# coin_cell_temp_sensor.net
KiCad netlist of a schematic drawn in EAGLE
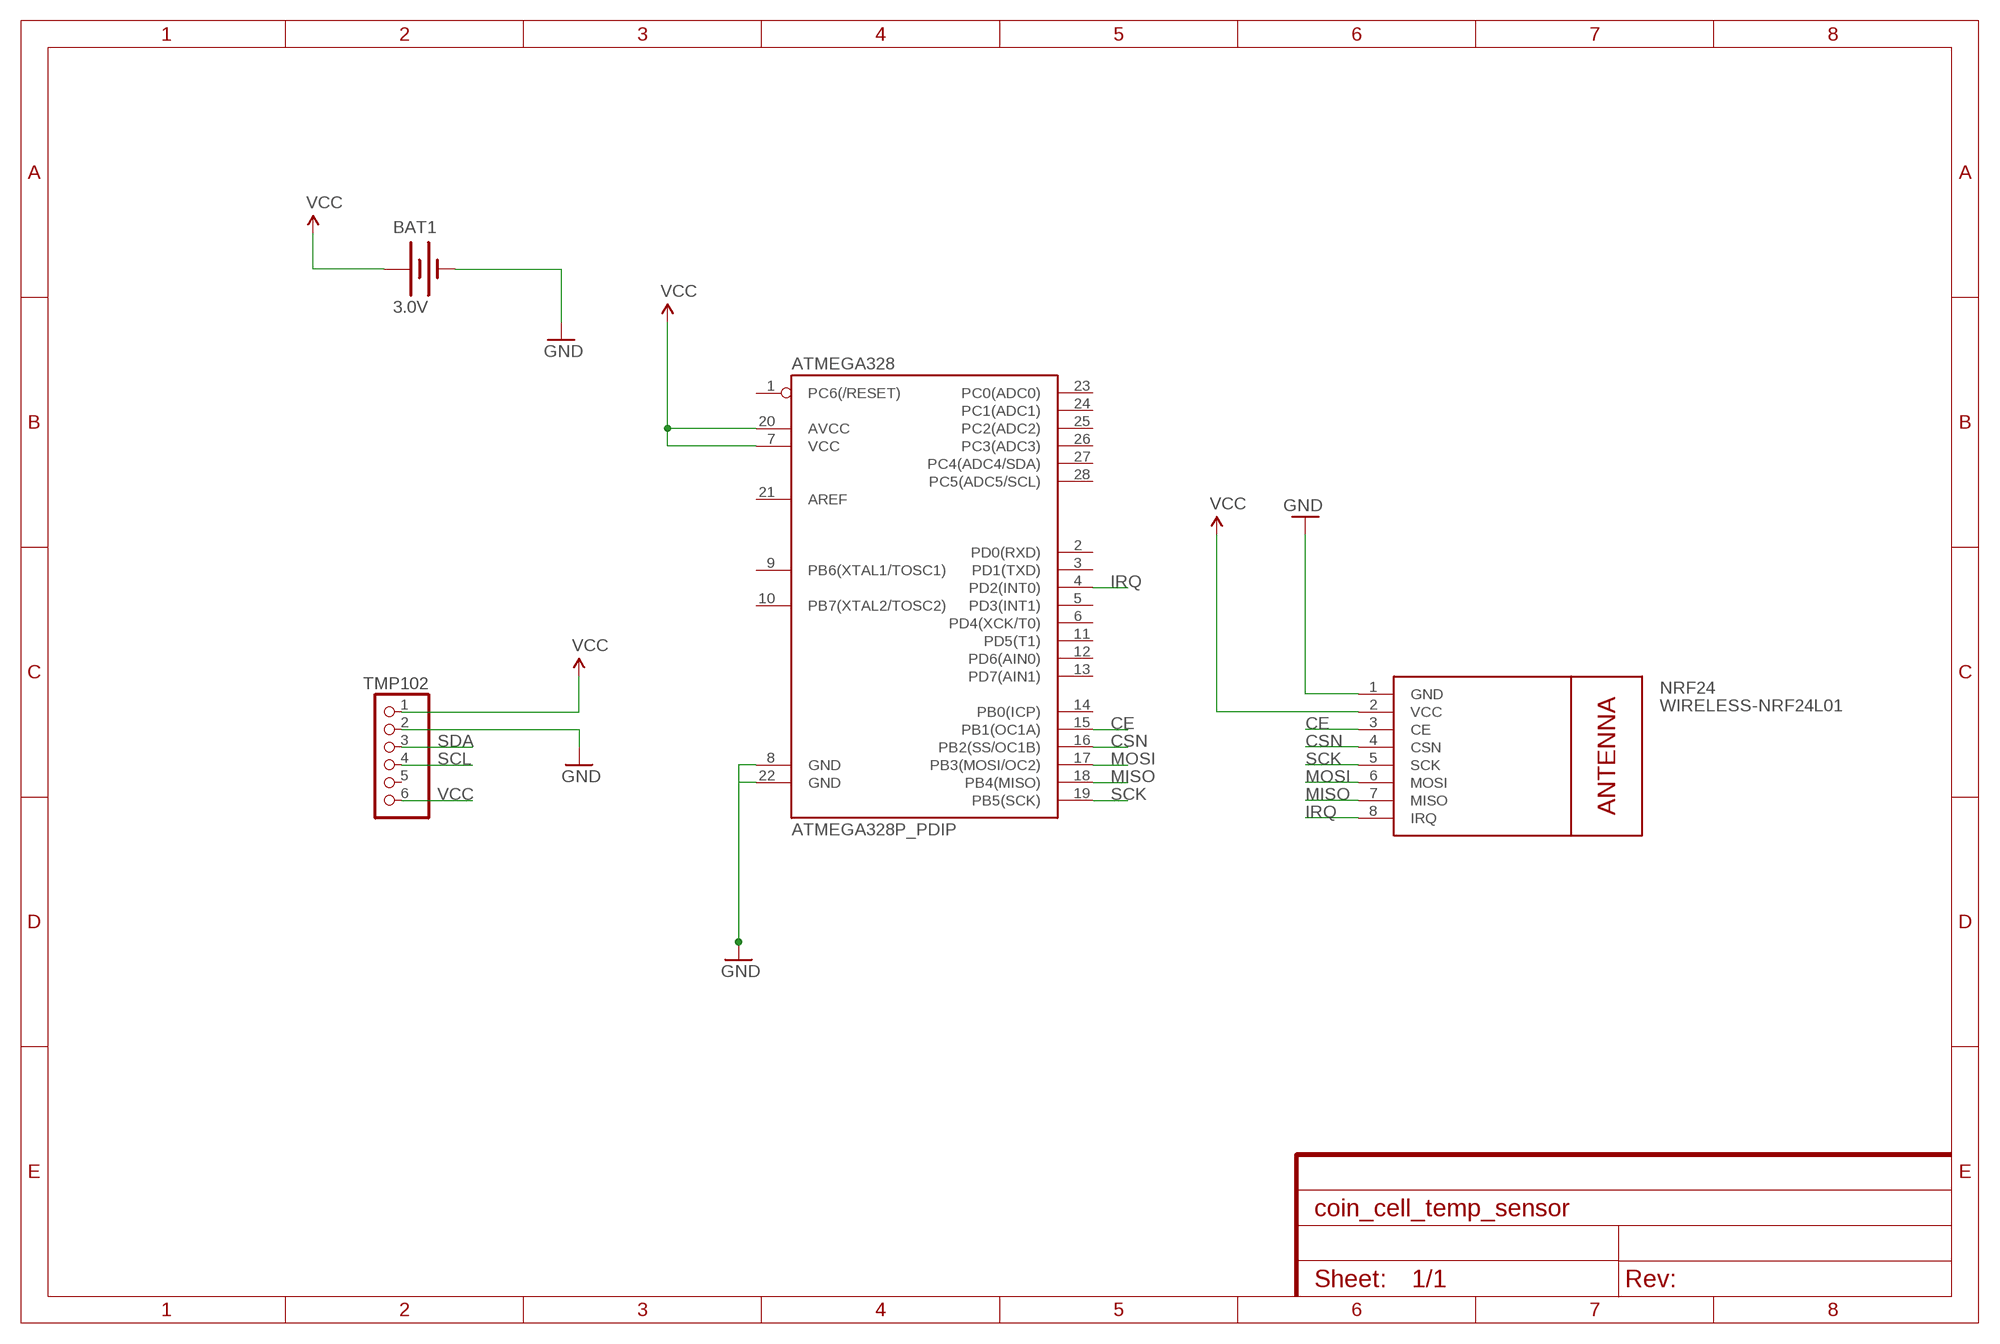
[diagram p0: schematic, sheet 1]

(export (version "E")
  (design (tool "Eeschema 10.0.6"))
  (components
    (comp (ref "ATMEGA328")
      (value "ATMEGA328P_PDIP")
      (footprint "eagle-import:DIL28-3")
      (libsource (lib "eagle-import") (part "ATMEGA328P_PDIP"))
    )
    (comp (ref "BAT1")
      (value "3.0V")
      (footprint "eagle-import:BATTCON_245MM_PTH")
      (libsource (lib "eagle-import") (part "BATTERY245PTH"))
    )
    (comp (ref "NRF24")
      (value "WIRELESS-NRF24L01")
      (footprint "eagle-import:WIRELESS-NRF24L01")
      (libsource (lib "eagle-import") (part "WIRELESS-NRF24L01"))
    )
    (comp (ref "TMP102")
      (value "PINHD-1X6")
      (footprint "eagle-import:1X06")
      (libsource (lib "eagle-import") (part "PINHD-1X6"))
    )
  )
  (nets
    (net (code "1") (name "/CE") (class "Default")
      (node (ref "ATMEGA328") (pin "15") (pinfunction "PB1(OC1A)_15") (pintype "bidirectional"))
      (node (ref "NRF24") (pin "3") (pinfunction "CE_3") (pintype "bidirectional"))
    )
    (net (code "2") (name "/CSN") (class "Default")
      (node (ref "ATMEGA328") (pin "16") (pinfunction "PB2(SS/OC1B)_16") (pintype "bidirectional"))
      (node (ref "NRF24") (pin "4") (pinfunction "CSN_4") (pintype "bidirectional"))
    )
    (net (code "3") (name "/IRQ") (class "Default")
      (node (ref "ATMEGA328") (pin "4") (pinfunction "PD2(INT0)_4") (pintype "bidirectional"))
      (node (ref "NRF24") (pin "8") (pinfunction "IRQ_8") (pintype "bidirectional"))
    )
    (net (code "4") (name "/MISO") (class "Default")
      (node (ref "ATMEGA328") (pin "18") (pinfunction "PB4(MISO)_18") (pintype "bidirectional"))
      (node (ref "NRF24") (pin "7") (pinfunction "MISO_7") (pintype "bidirectional"))
    )
    (net (code "5") (name "/MOSI") (class "Default")
      (node (ref "ATMEGA328") (pin "17") (pinfunction "PB3(MOSI/OC2)_17") (pintype "bidirectional"))
      (node (ref "NRF24") (pin "6") (pinfunction "MOSI_6") (pintype "bidirectional"))
    )
    (net (code "6") (name "/SCK") (class "Default")
      (node (ref "ATMEGA328") (pin "19") (pinfunction "PB5(SCK)_19") (pintype "bidirectional"))
      (node (ref "NRF24") (pin "5") (pinfunction "SCK_5") (pintype "bidirectional"))
    )
    (net (code "7") (name "/SCL") (class "Default")
      (node (ref "TMP102") (pin "4") (pinfunction "4_4") (pintype "passive"))
    )
    (net (code "8") (name "/SDA") (class "Default")
      (node (ref "TMP102") (pin "3") (pinfunction "3_3") (pintype "passive"))
    )
    (net (code "9") (name "GND") (class "Default")
      (node (ref "ATMEGA328") (pin "22") (pinfunction "GND_22") (pintype "bidirectional"))
      (node (ref "ATMEGA328") (pin "8") (pinfunction "GND_8") (pintype "bidirectional"))
      (node (ref "BAT1") (pin "2") (pinfunction "-_2") (pintype "power_in"))
      (node (ref "NRF24") (pin "1") (pinfunction "GND_1") (pintype "power_in"))
      (node (ref "TMP102") (pin "2") (pinfunction "2_2") (pintype "passive"))
    )
    (net (code "10") (name "VCC") (class "Default")
      (node (ref "ATMEGA328") (pin "20") (pinfunction "AVCC_20") (pintype "bidirectional"))
      (node (ref "ATMEGA328") (pin "7") (pinfunction "VCC_7") (pintype "bidirectional"))
      (node (ref "BAT1") (pin "3") (pinfunction "+_3") (pintype "power_in"))
      (node (ref "NRF24") (pin "2") (pinfunction "VCC_2") (pintype "power_in"))
      (node (ref "TMP102") (pin "1") (pinfunction "1_1") (pintype "passive"))
      (node (ref "TMP102") (pin "6") (pinfunction "6_6") (pintype "passive"))
    )
    (net (code "11") (name "unconnected-(ATMEGA328-AREF-Pad21)") (class "Default")
      (node (ref "ATMEGA328") (pin "21") (pinfunction "AREF_21") (pintype "bidirectional"))
    )
    (net (code "12") (name "unconnected-(ATMEGA328-PB0(ICP)-Pad14)") (class "Default")
      (node (ref "ATMEGA328") (pin "14") (pinfunction "PB0(ICP)_14") (pintype "bidirectional"))
    )
    (net (code "13") (name "unconnected-(ATMEGA328-PB6(XTAL1{slash}TOSC1)-Pad9)") (class "Default")
      (node (ref "ATMEGA328") (pin "9") (pinfunction "PB6(XTAL1/TOSC1)_9") (pintype "bidirectional"))
    )
    (net (code "14") (name "unconnected-(ATMEGA328-PB7(XTAL2{slash}TOSC2)-Pad10)") (class "Default")
      (node (ref "ATMEGA328") (pin "10") (pinfunction "PB7(XTAL2/TOSC2)_10") (pintype "bidirectional"))
    )
    (net (code "15") (name "unconnected-(ATMEGA328-PC0(ADC0)-Pad23)") (class "Default")
      (node (ref "ATMEGA328") (pin "23") (pinfunction "PC0(ADC0)_23") (pintype "bidirectional"))
    )
    (net (code "16") (name "unconnected-(ATMEGA328-PC1(ADC1)-Pad24)") (class "Default")
      (node (ref "ATMEGA328") (pin "24") (pinfunction "PC1(ADC1)_24") (pintype "bidirectional"))
    )
    (net (code "17") (name "unconnected-(ATMEGA328-PC2(ADC2)-Pad25)") (class "Default")
      (node (ref "ATMEGA328") (pin "25") (pinfunction "PC2(ADC2)_25") (pintype "bidirectional"))
    )
    (net (code "18") (name "unconnected-(ATMEGA328-PC3(ADC3)-Pad26)") (class "Default")
      (node (ref "ATMEGA328") (pin "26") (pinfunction "PC3(ADC3)_26") (pintype "bidirectional"))
    )
    (net (code "19") (name "unconnected-(ATMEGA328-PC4(ADC4{slash}SDA)-Pad27)") (class "Default")
      (node (ref "ATMEGA328") (pin "27") (pinfunction "PC4(ADC4/SDA)_27") (pintype "bidirectional"))
    )
    (net (code "20") (name "unconnected-(ATMEGA328-PC5(ADC5{slash}SCL)-Pad28)") (class "Default")
      (node (ref "ATMEGA328") (pin "28") (pinfunction "PC5(ADC5/SCL)_28") (pintype "bidirectional"))
    )
    (net (code "21") (name "unconnected-(ATMEGA328-PC6({slash}RESET)-Pad1)") (class "Default")
      (node (ref "ATMEGA328") (pin "1") (pinfunction "PC6(/RESET)_1") (pintype "bidirectional"))
    )
    (net (code "22") (name "unconnected-(ATMEGA328-PD0(RXD)-Pad2)") (class "Default")
      (node (ref "ATMEGA328") (pin "2") (pinfunction "PD0(RXD)_2") (pintype "bidirectional"))
    )
    (net (code "23") (name "unconnected-(ATMEGA328-PD1(TXD)-Pad3)") (class "Default")
      (node (ref "ATMEGA328") (pin "3") (pinfunction "PD1(TXD)_3") (pintype "bidirectional"))
    )
    (net (code "24") (name "unconnected-(ATMEGA328-PD3(INT1)-Pad5)") (class "Default")
      (node (ref "ATMEGA328") (pin "5") (pinfunction "PD3(INT1)_5") (pintype "bidirectional"))
    )
    (net (code "25") (name "unconnected-(ATMEGA328-PD4(XCK{slash}T0)-Pad6)") (class "Default")
      (node (ref "ATMEGA328") (pin "6") (pinfunction "PD4(XCK/T0)_6") (pintype "bidirectional"))
    )
    (net (code "26") (name "unconnected-(ATMEGA328-PD5(T1)-Pad11)") (class "Default")
      (node (ref "ATMEGA328") (pin "11") (pinfunction "PD5(T1)_11") (pintype "bidirectional"))
    )
    (net (code "27") (name "unconnected-(ATMEGA328-PD6(AIN0)-Pad12)") (class "Default")
      (node (ref "ATMEGA328") (pin "12") (pinfunction "PD6(AIN0)_12") (pintype "bidirectional"))
    )
    (net (code "28") (name "unconnected-(ATMEGA328-PD7(AIN1)-Pad13)") (class "Default")
      (node (ref "ATMEGA328") (pin "13") (pinfunction "PD7(AIN1)_13") (pintype "bidirectional"))
    )
    (net (code "29") (name "unconnected-(TMP102-Pad5)") (class "Default")
      (node (ref "TMP102") (pin "5") (pinfunction "5_5") (pintype "passive"))
    )
  )
)
